# TD_0002-100_3.net
KiCad netlist of a schematic drawn in Altium Designer
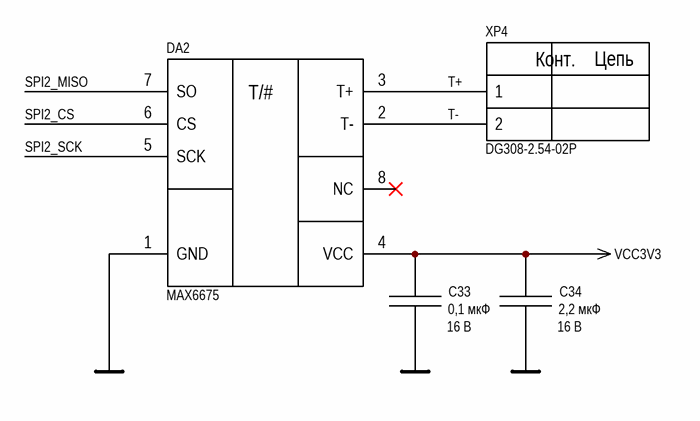
[diagram p0: TD.0002-100_3.SchDoc]

(export (version "E")
  (design (tool "Eeschema 10.0.6"))
  (components
    (comp (ref "C33")
      (value "0,1 мкФ")
      (footprint "C_0402")
      (description "Chip Multilayer Ceramic Capacitor")
      (fields
        (field (name "PART NUMBER") "GRM155R61C104KA88")
        (field (name "MANUFACTURER") "Murata")
        (field (name "VOLTAGE") "16 В")
      )
      (libsource (lib "Database_Libs") (part "Capacitor"))
    )
    (comp (ref "C34")
      (value "2,2 мкФ")
      (footprint "C_0402")
      (description "Chip Multilayer Ceramic Capacitor")
      (fields
        (field (name "PART NUMBER") "GRM155R61C225KE11")
        (field (name "MANUFACTURER") "Murata")
        (field (name "VOLTAGE") "16 В")
      )
      (libsource (lib "Database_Libs") (part "Capacitor"))
    )
    (comp (ref "DA2")
      (value "MAX6675")
      (footprint "FirstLib:SOIC-8")
      (fields (field (name "MANUFACTURER") "Maxim Integrated"))
      (libsource (lib "FirstLib") (part "MAX6675"))
    )
    (comp (ref "XP4")
      (value "DG308-2.54-02P")
      (footprint "FirstLib:Terminal_Block_2PIN")
      (fields (field (name "MANUFACTURER") "Dinkle") (field (name "VOLTAGE") "250 V"))
      (libsource (lib "FirstLib") (part "DG308-2.54-02P-14-00AH"))
    )
  )
  (nets
    (net (code "1") (name "/SPI2_CS") (class "Default")
      (node (ref "DA2") (pin "6") (pinfunction "CS_6") (pintype "passive"))
    )
    (net (code "2") (name "/SPI2_MISO") (class "Default")
      (node (ref "DA2") (pin "7") (pinfunction "SO_7") (pintype "passive"))
    )
    (net (code "3") (name "/SPI2_SCK") (class "Default")
      (node (ref "DA2") (pin "5") (pinfunction "SCK_5") (pintype "passive"))
    )
    (net (code "4") (name "/T+") (class "Default")
      (node (ref "DA2") (pin "3") (pinfunction "T+_3") (pintype "passive"))
      (node (ref "XP4") (pin "1") (pinfunction "1_1") (pintype "passive"))
    )
    (net (code "5") (name "/T-") (class "Default")
      (node (ref "DA2") (pin "2") (pinfunction "T-_2") (pintype "passive"))
      (node (ref "XP4") (pin "2") (pinfunction "2_2") (pintype "passive"))
    )
    (net (code "6") (name "GND") (class "Default")
      (node (ref "C33") (pin "2") (pinfunction "2_2") (pintype "passive"))
      (node (ref "C34") (pin "2") (pinfunction "2_2") (pintype "passive"))
      (node (ref "DA2") (pin "1") (pinfunction "GND_1") (pintype "passive"))
    )
    (net (code "7") (name "VCC3V3") (class "Default")
      (node (ref "C33") (pin "1") (pinfunction "1_1") (pintype "passive"))
      (node (ref "C34") (pin "1") (pinfunction "1_1") (pintype "passive"))
      (node (ref "DA2") (pin "4") (pinfunction "VCC_4") (pintype "passive"))
    )
    (net (code "8") (name "unconnected-(DA2-NC-Pad8)") (class "Default")
      (node (ref "DA2") (pin "8") (pinfunction "NC_8") (pintype "passive+no_connect"))
    )
  )
)
